# LightPlay1_1.net
KiCad netlist of a schematic drawn in EAGLE
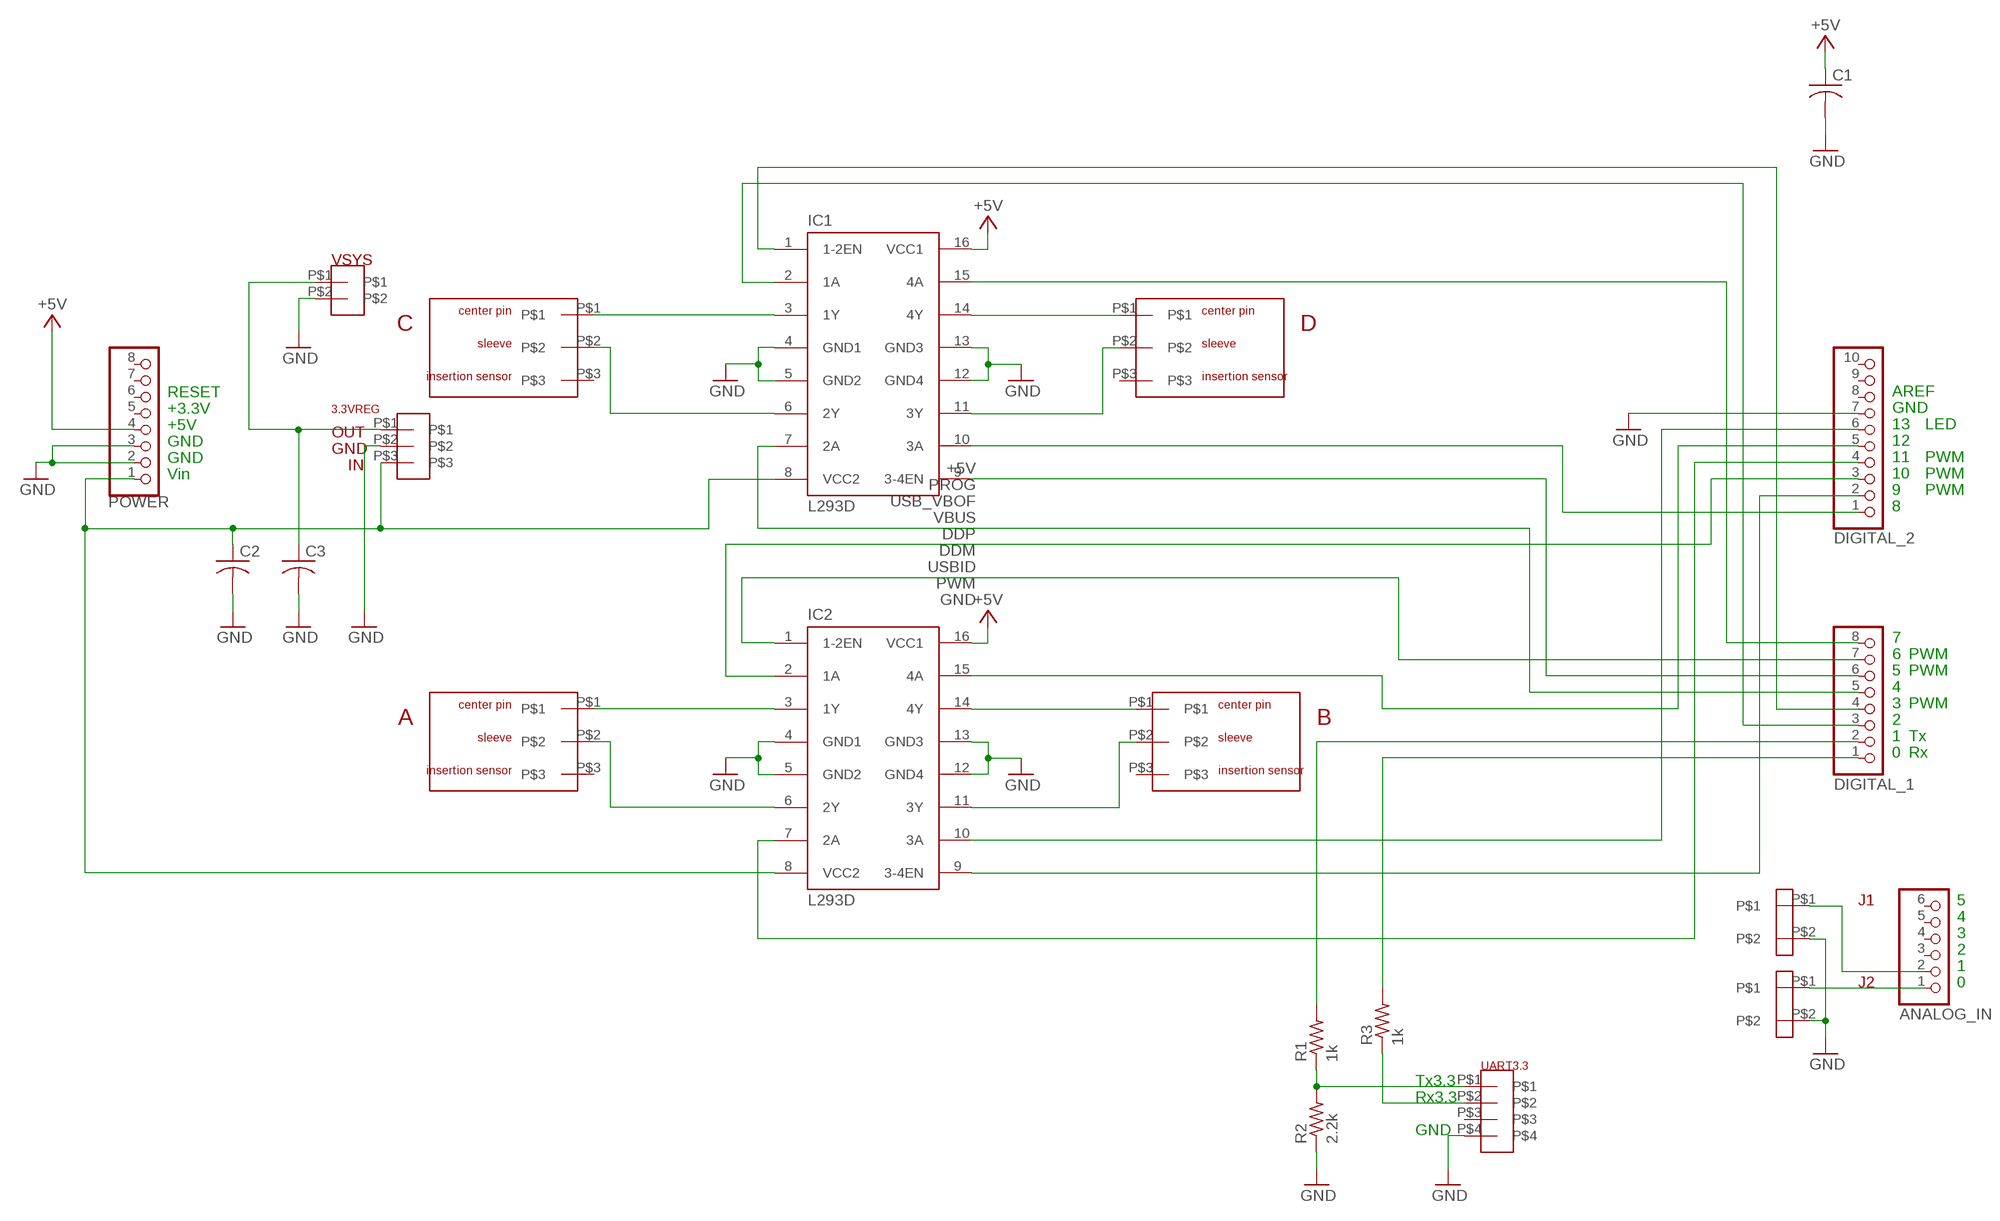
[diagram p0: schematic, sheet 1]

(export (version "E")
  (design (tool "Eeschema 10.0.6"))
  (components
    (comp (ref "3.3VREG")
      (value "LP38691_33REG")
      (footprint "eagle-import:TO-252")
      (libsource (lib "eagle-import") (part "LP38691_33REG"))
    )
    (comp (ref "A")
      (value "PJ-075DH-SMT-TR")
      (footprint "eagle-import:PJ-075DH-SMT-TR")
      (libsource (lib "eagle-import") (part "PJ-075DH-SMT-TR"))
    )
    (comp (ref "ANALOG_IN")
      (value "PINHD-1X6TH")
      (footprint "eagle-import:1X06-TH")
      (libsource (lib "eagle-import") (part "PINHD-1X6TH"))
    )
    (comp (ref "B")
      (value "PJ-075DH-SMT-TR")
      (footprint "eagle-import:PJ-075DH-SMT-TR")
      (libsource (lib "eagle-import") (part "PJ-075DH-SMT-TR"))
    )
    (comp (ref "C")
      (value "PJ-075DH-SMT-TR")
      (footprint "eagle-import:PJ-075DH-SMT-TR")
      (libsource (lib "eagle-import") (part "PJ-075DH-SMT-TR"))
    )
    (comp (ref "C1")
      (value "C-USC1206")
      (footprint "eagle-import:C1206")
      (libsource (lib "eagle-import") (part "C-USC1206"))
    )
    (comp (ref "C2")
      (value "C-USC1206")
      (footprint "eagle-import:C1206")
      (libsource (lib "eagle-import") (part "C-USC1206"))
    )
    (comp (ref "C3")
      (value "C-USC1206")
      (footprint "eagle-import:C1206")
      (libsource (lib "eagle-import") (part "C-USC1206"))
    )
    (comp (ref "D")
      (value "PJ-075DH-SMT-TR")
      (footprint "eagle-import:PJ-075DH-SMT-TR")
      (libsource (lib "eagle-import") (part "PJ-075DH-SMT-TR"))
    )
    (comp (ref "DIGITAL_1")
      (value "PINHD-1X8TH")
      (footprint "eagle-import:1X08-TH")
      (libsource (lib "eagle-import") (part "PINHD-1X8TH"))
    )
    (comp (ref "DIGITAL_2")
      (value "PINHD-1X10TH")
      (footprint "eagle-import:1X10-TH")
      (libsource (lib "eagle-import") (part "PINHD-1X10TH"))
    )
    (comp (ref "IC1")
      (value "L293D")
      (footprint "eagle-import:DIL16")
      (libsource (lib "eagle-import") (part "L293D"))
    )
    (comp (ref "IC2")
      (value "L293D")
      (footprint "eagle-import:DIL16")
      (libsource (lib "eagle-import") (part "L293D"))
    )
    (comp (ref "J1")
      (value "3.5MM_2PIN_SCREWTERMINAL_SPARKFUN")
      (footprint "eagle-import:1X02_3.5_SCREWTERM")
      (libsource (lib "eagle-import") (part "3.5MM_2PIN_SCREWTERMINAL_SPARKFUN"))
    )
    (comp (ref "J2")
      (value "3.5MM_2PIN_SCREWTERMINAL_SPARKFUN")
      (footprint "eagle-import:1X02_3.5_SCREWTERM")
      (libsource (lib "eagle-import") (part "3.5MM_2PIN_SCREWTERMINAL_SPARKFUN"))
    )
    (comp (ref "POWER")
      (value "PINHD-1X8TH")
      (footprint "eagle-import:1X08-TH")
      (libsource (lib "eagle-import") (part "PINHD-1X8TH"))
    )
    (comp (ref "R1")
      (value "1k")
      (footprint "eagle-import:M1206")
      (libsource (lib "eagle-import") (part "R-US_M1206"))
    )
    (comp (ref "R2")
      (value "2.2k")
      (footprint "eagle-import:M1206")
      (libsource (lib "eagle-import") (part "R-US_M1206"))
    )
    (comp (ref "R3")
      (value "1k")
      (footprint "eagle-import:M1206")
      (libsource (lib "eagle-import") (part "R-US_M1206"))
    )
    (comp (ref "UART3.3")
      (value "4PADS_ROBBIE")
      (footprint "eagle-import:1X04_ROBBIE")
      (libsource (lib "eagle-import") (part "4PADS_ROBBIE"))
    )
    (comp (ref "VSYS")
      (value "1X2HEADER_ROBBIE")
      (footprint "eagle-import:1X2HEADER_ROBBIE")
      (libsource (lib "eagle-import") (part "1X2HEADER_ROBBIE"))
    )
  )
  (nets
    (net (code "1") (name "+5V") (class "Default")
      (node (ref "C1") (pin "1") (pinfunction "1_1") (pintype "passive"))
      (node (ref "IC1") (pin "16") (pinfunction "VCC1_16") (pintype "power_in"))
      (node (ref "IC2") (pin "16") (pinfunction "VCC1_16") (pintype "power_in"))
      (node (ref "POWER") (pin "4") (pinfunction "4_4") (pintype "passive"))
    )
    (net (code "2") (name "GND") (class "Default")
      (node (ref "3.3VREG") (pin "P$2") (pinfunction "P$2_P$2") (pintype "bidirectional"))
      (node (ref "C1") (pin "2") (pinfunction "2_2") (pintype "passive"))
      (node (ref "C2") (pin "2") (pinfunction "2_2") (pintype "passive"))
      (node (ref "C3") (pin "2") (pinfunction "2_2") (pintype "passive"))
      (node (ref "DIGITAL_2") (pin "7") (pinfunction "7_7") (pintype "passive"))
      (node (ref "IC1") (pin "12") (pinfunction "GND4_12") (pintype "power_in"))
      (node (ref "IC1") (pin "13") (pinfunction "GND3_13") (pintype "power_in"))
      (node (ref "IC1") (pin "4") (pinfunction "GND1_4") (pintype "power_in"))
      (node (ref "IC1") (pin "5") (pinfunction "GND2_5") (pintype "power_in"))
      (node (ref "IC2") (pin "12") (pinfunction "GND4_12") (pintype "power_in"))
      (node (ref "IC2") (pin "13") (pinfunction "GND3_13") (pintype "power_in"))
      (node (ref "IC2") (pin "4") (pinfunction "GND1_4") (pintype "power_in"))
      (node (ref "IC2") (pin "5") (pinfunction "GND2_5") (pintype "power_in"))
      (node (ref "J1") (pin "P$2") (pinfunction "P$2_P$2") (pintype "bidirectional"))
      (node (ref "J2") (pin "P$2") (pinfunction "P$2_P$2") (pintype "bidirectional"))
      (node (ref "POWER") (pin "2") (pinfunction "2_2") (pintype "passive"))
      (node (ref "POWER") (pin "3") (pinfunction "3_3") (pintype "passive"))
      (node (ref "R2") (pin "1") (pinfunction "1_1") (pintype "passive"))
      (node (ref "UART3.3") (pin "P$4") (pinfunction "P$4_P$4") (pintype "bidirectional"))
      (node (ref "VSYS") (pin "P$2") (pinfunction "P$2_P$2") (pintype "bidirectional"))
    )
    (net (code "3") (name "Net-(3.3VREG-PadP$1)") (class "Default")
      (node (ref "3.3VREG") (pin "P$1") (pinfunction "P$1_P$1") (pintype "bidirectional"))
      (node (ref "C3") (pin "1") (pinfunction "1_1") (pintype "passive"))
      (node (ref "VSYS") (pin "P$1") (pinfunction "P$1_P$1") (pintype "bidirectional"))
    )
    (net (code "4") (name "Net-(ANALOG_IN-Pad1)") (class "Default")
      (node (ref "ANALOG_IN") (pin "1") (pinfunction "1_1") (pintype "passive"))
      (node (ref "J2") (pin "P$1") (pinfunction "P$1_P$1") (pintype "bidirectional"))
    )
    (net (code "5") (name "Net-(ANALOG_IN-Pad2)") (class "Default")
      (node (ref "ANALOG_IN") (pin "2") (pinfunction "2_2") (pintype "passive"))
      (node (ref "J1") (pin "P$1") (pinfunction "P$1_P$1") (pintype "bidirectional"))
    )
    (net (code "6") (name "Net-(DIGITAL_1-Pad1)") (class "Default")
      (node (ref "DIGITAL_1") (pin "1") (pinfunction "1_1") (pintype "passive"))
      (node (ref "R3") (pin "2") (pinfunction "2_2") (pintype "passive"))
    )
    (net (code "7") (name "Net-(DIGITAL_1-Pad2)") (class "Default")
      (node (ref "DIGITAL_1") (pin "2") (pinfunction "2_2") (pintype "passive"))
      (node (ref "R1") (pin "2") (pinfunction "2_2") (pintype "passive"))
    )
    (net (code "8") (name "Net-(IC1-1-2EN)") (class "Default")
      (node (ref "DIGITAL_1") (pin "4") (pinfunction "4_4") (pintype "passive"))
      (node (ref "IC1") (pin "1") (pinfunction "1-2EN_1") (pintype "input"))
    )
    (net (code "9") (name "Net-(IC1-1A)") (class "Default")
      (node (ref "DIGITAL_1") (pin "3") (pinfunction "3_3") (pintype "passive"))
      (node (ref "IC1") (pin "2") (pinfunction "1A_2") (pintype "input"))
    )
    (net (code "10") (name "Net-(IC1-1Y)") (class "Default")
      (node (ref "C") (pin "P$1") (pinfunction "P$1_P$1") (pintype "bidirectional"))
      (node (ref "IC1") (pin "3") (pinfunction "1Y_3") (pintype "output"))
    )
    (net (code "11") (name "Net-(IC1-2A)") (class "Default")
      (node (ref "DIGITAL_1") (pin "5") (pinfunction "5_5") (pintype "passive"))
      (node (ref "IC1") (pin "7") (pinfunction "2A_7") (pintype "input"))
    )
    (net (code "12") (name "Net-(IC1-2Y)") (class "Default")
      (node (ref "C") (pin "P$2") (pinfunction "P$2_P$2") (pintype "bidirectional"))
      (node (ref "IC1") (pin "6") (pinfunction "2Y_6") (pintype "output"))
    )
    (net (code "13") (name "Net-(IC1-3-4EN)") (class "Default")
      (node (ref "DIGITAL_1") (pin "6") (pinfunction "6_6") (pintype "passive"))
      (node (ref "IC1") (pin "9") (pinfunction "3-4EN_9") (pintype "input"))
    )
    (net (code "14") (name "Net-(IC1-3A)") (class "Default")
      (node (ref "DIGITAL_2") (pin "1") (pinfunction "1_1") (pintype "passive"))
      (node (ref "IC1") (pin "10") (pinfunction "3A_10") (pintype "input"))
    )
    (net (code "15") (name "Net-(IC1-3Y)") (class "Default")
      (node (ref "D") (pin "P$2") (pinfunction "P$2_P$2") (pintype "bidirectional"))
      (node (ref "IC1") (pin "11") (pinfunction "3Y_11") (pintype "output"))
    )
    (net (code "16") (name "Net-(IC1-4A)") (class "Default")
      (node (ref "DIGITAL_1") (pin "8") (pinfunction "8_8") (pintype "passive"))
      (node (ref "IC1") (pin "15") (pinfunction "4A_15") (pintype "input"))
    )
    (net (code "17") (name "Net-(IC1-4Y)") (class "Default")
      (node (ref "D") (pin "P$1") (pinfunction "P$1_P$1") (pintype "bidirectional"))
      (node (ref "IC1") (pin "14") (pinfunction "4Y_14") (pintype "output"))
    )
    (net (code "18") (name "Net-(IC1-VCC2)") (class "Default")
      (node (ref "3.3VREG") (pin "P$3") (pinfunction "P$3_P$3") (pintype "bidirectional"))
      (node (ref "C2") (pin "1") (pinfunction "1_1") (pintype "passive"))
      (node (ref "IC1") (pin "8") (pinfunction "VCC2_8") (pintype "power_in"))
      (node (ref "IC2") (pin "8") (pinfunction "VCC2_8") (pintype "power_in"))
      (node (ref "POWER") (pin "1") (pinfunction "1_1") (pintype "passive"))
    )
    (net (code "19") (name "Net-(IC2-1-2EN)") (class "Default")
      (node (ref "DIGITAL_1") (pin "7") (pinfunction "7_7") (pintype "passive"))
      (node (ref "IC2") (pin "1") (pinfunction "1-2EN_1") (pintype "input"))
    )
    (net (code "20") (name "Net-(IC2-1A)") (class "Default")
      (node (ref "DIGITAL_2") (pin "3") (pinfunction "3_3") (pintype "passive"))
      (node (ref "IC2") (pin "2") (pinfunction "1A_2") (pintype "input"))
    )
    (net (code "21") (name "Net-(IC2-1Y)") (class "Default")
      (node (ref "A") (pin "P$1") (pinfunction "P$1_P$1") (pintype "bidirectional"))
      (node (ref "IC2") (pin "3") (pinfunction "1Y_3") (pintype "output"))
    )
    (net (code "22") (name "Net-(IC2-2A)") (class "Default")
      (node (ref "DIGITAL_2") (pin "4") (pinfunction "4_4") (pintype "passive"))
      (node (ref "IC2") (pin "7") (pinfunction "2A_7") (pintype "input"))
    )
    (net (code "23") (name "Net-(IC2-2Y)") (class "Default")
      (node (ref "A") (pin "P$2") (pinfunction "P$2_P$2") (pintype "bidirectional"))
      (node (ref "IC2") (pin "6") (pinfunction "2Y_6") (pintype "output"))
    )
    (net (code "24") (name "Net-(IC2-3-4EN)") (class "Default")
      (node (ref "DIGITAL_2") (pin "2") (pinfunction "2_2") (pintype "passive"))
      (node (ref "IC2") (pin "9") (pinfunction "3-4EN_9") (pintype "input"))
    )
    (net (code "25") (name "Net-(IC2-3A)") (class "Default")
      (node (ref "DIGITAL_2") (pin "6") (pinfunction "6_6") (pintype "passive"))
      (node (ref "IC2") (pin "10") (pinfunction "3A_10") (pintype "input"))
    )
    (net (code "26") (name "Net-(IC2-3Y)") (class "Default")
      (node (ref "B") (pin "P$2") (pinfunction "P$2_P$2") (pintype "bidirectional"))
      (node (ref "IC2") (pin "11") (pinfunction "3Y_11") (pintype "output"))
    )
    (net (code "27") (name "Net-(IC2-4A)") (class "Default")
      (node (ref "DIGITAL_2") (pin "5") (pinfunction "5_5") (pintype "passive"))
      (node (ref "IC2") (pin "15") (pinfunction "4A_15") (pintype "input"))
    )
    (net (code "28") (name "Net-(IC2-4Y)") (class "Default")
      (node (ref "B") (pin "P$1") (pinfunction "P$1_P$1") (pintype "bidirectional"))
      (node (ref "IC2") (pin "14") (pinfunction "4Y_14") (pintype "output"))
    )
    (net (code "29") (name "Net-(R1-Pad1)") (class "Default")
      (node (ref "R1") (pin "1") (pinfunction "1_1") (pintype "passive"))
      (node (ref "R2") (pin "2") (pinfunction "2_2") (pintype "passive"))
      (node (ref "UART3.3") (pin "P$1") (pinfunction "P$1_P$1") (pintype "bidirectional"))
    )
    (net (code "30") (name "Net-(R3-Pad1)") (class "Default")
      (node (ref "R3") (pin "1") (pinfunction "1_1") (pintype "passive"))
      (node (ref "UART3.3") (pin "P$2") (pinfunction "P$2_P$2") (pintype "bidirectional"))
    )
    (net (code "31") (name "unconnected-(A-PadP$3)") (class "Default")
      (node (ref "A") (pin "P$3") (pinfunction "P$3_P$3") (pintype "bidirectional"))
    )
    (net (code "32") (name "unconnected-(ANALOG_IN-Pad3)") (class "Default")
      (node (ref "ANALOG_IN") (pin "3") (pinfunction "3_3") (pintype "passive"))
    )
    (net (code "33") (name "unconnected-(ANALOG_IN-Pad4)") (class "Default")
      (node (ref "ANALOG_IN") (pin "4") (pinfunction "4_4") (pintype "passive"))
    )
    (net (code "34") (name "unconnected-(ANALOG_IN-Pad5)") (class "Default")
      (node (ref "ANALOG_IN") (pin "5") (pinfunction "5_5") (pintype "passive"))
    )
    (net (code "35") (name "unconnected-(ANALOG_IN-Pad6)") (class "Default")
      (node (ref "ANALOG_IN") (pin "6") (pinfunction "6_6") (pintype "passive"))
    )
    (net (code "36") (name "unconnected-(B-PadP$3)") (class "Default")
      (node (ref "B") (pin "P$3") (pinfunction "P$3_P$3") (pintype "bidirectional"))
    )
    (net (code "37") (name "unconnected-(C-PadP$3)") (class "Default")
      (node (ref "C") (pin "P$3") (pinfunction "P$3_P$3") (pintype "bidirectional"))
    )
    (net (code "38") (name "unconnected-(D-PadP$3)") (class "Default")
      (node (ref "D") (pin "P$3") (pinfunction "P$3_P$3") (pintype "bidirectional"))
    )
    (net (code "39") (name "unconnected-(DIGITAL_2-Pad8)") (class "Default")
      (node (ref "DIGITAL_2") (pin "8") (pinfunction "8_8") (pintype "passive"))
    )
    (net (code "40") (name "unconnected-(DIGITAL_2-Pad9)") (class "Default")
      (node (ref "DIGITAL_2") (pin "9") (pinfunction "9_9") (pintype "passive"))
    )
    (net (code "41") (name "unconnected-(DIGITAL_2-Pad10)") (class "Default")
      (node (ref "DIGITAL_2") (pin "10") (pinfunction "10_10") (pintype "passive"))
    )
    (net (code "42") (name "unconnected-(POWER-Pad5)") (class "Default")
      (node (ref "POWER") (pin "5") (pinfunction "5_5") (pintype "passive"))
    )
    (net (code "43") (name "unconnected-(POWER-Pad6)") (class "Default")
      (node (ref "POWER") (pin "6") (pinfunction "6_6") (pintype "passive"))
    )
    (net (code "44") (name "unconnected-(POWER-Pad7)") (class "Default")
      (node (ref "POWER") (pin "7") (pinfunction "7_7") (pintype "passive"))
    )
    (net (code "45") (name "unconnected-(POWER-Pad8)") (class "Default")
      (node (ref "POWER") (pin "8") (pinfunction "8_8") (pintype "passive"))
    )
    (net (code "46") (name "unconnected-(UART3.3-PadP$3)") (class "Default")
      (node (ref "UART3.3") (pin "P$3") (pinfunction "P$3_P$3") (pintype "bidirectional"))
    )
  )
)
